# SCH_MIW_PS_on_PCB_2021-12-30.net
KiCad netlist of a schematic drawn in EasyEDA
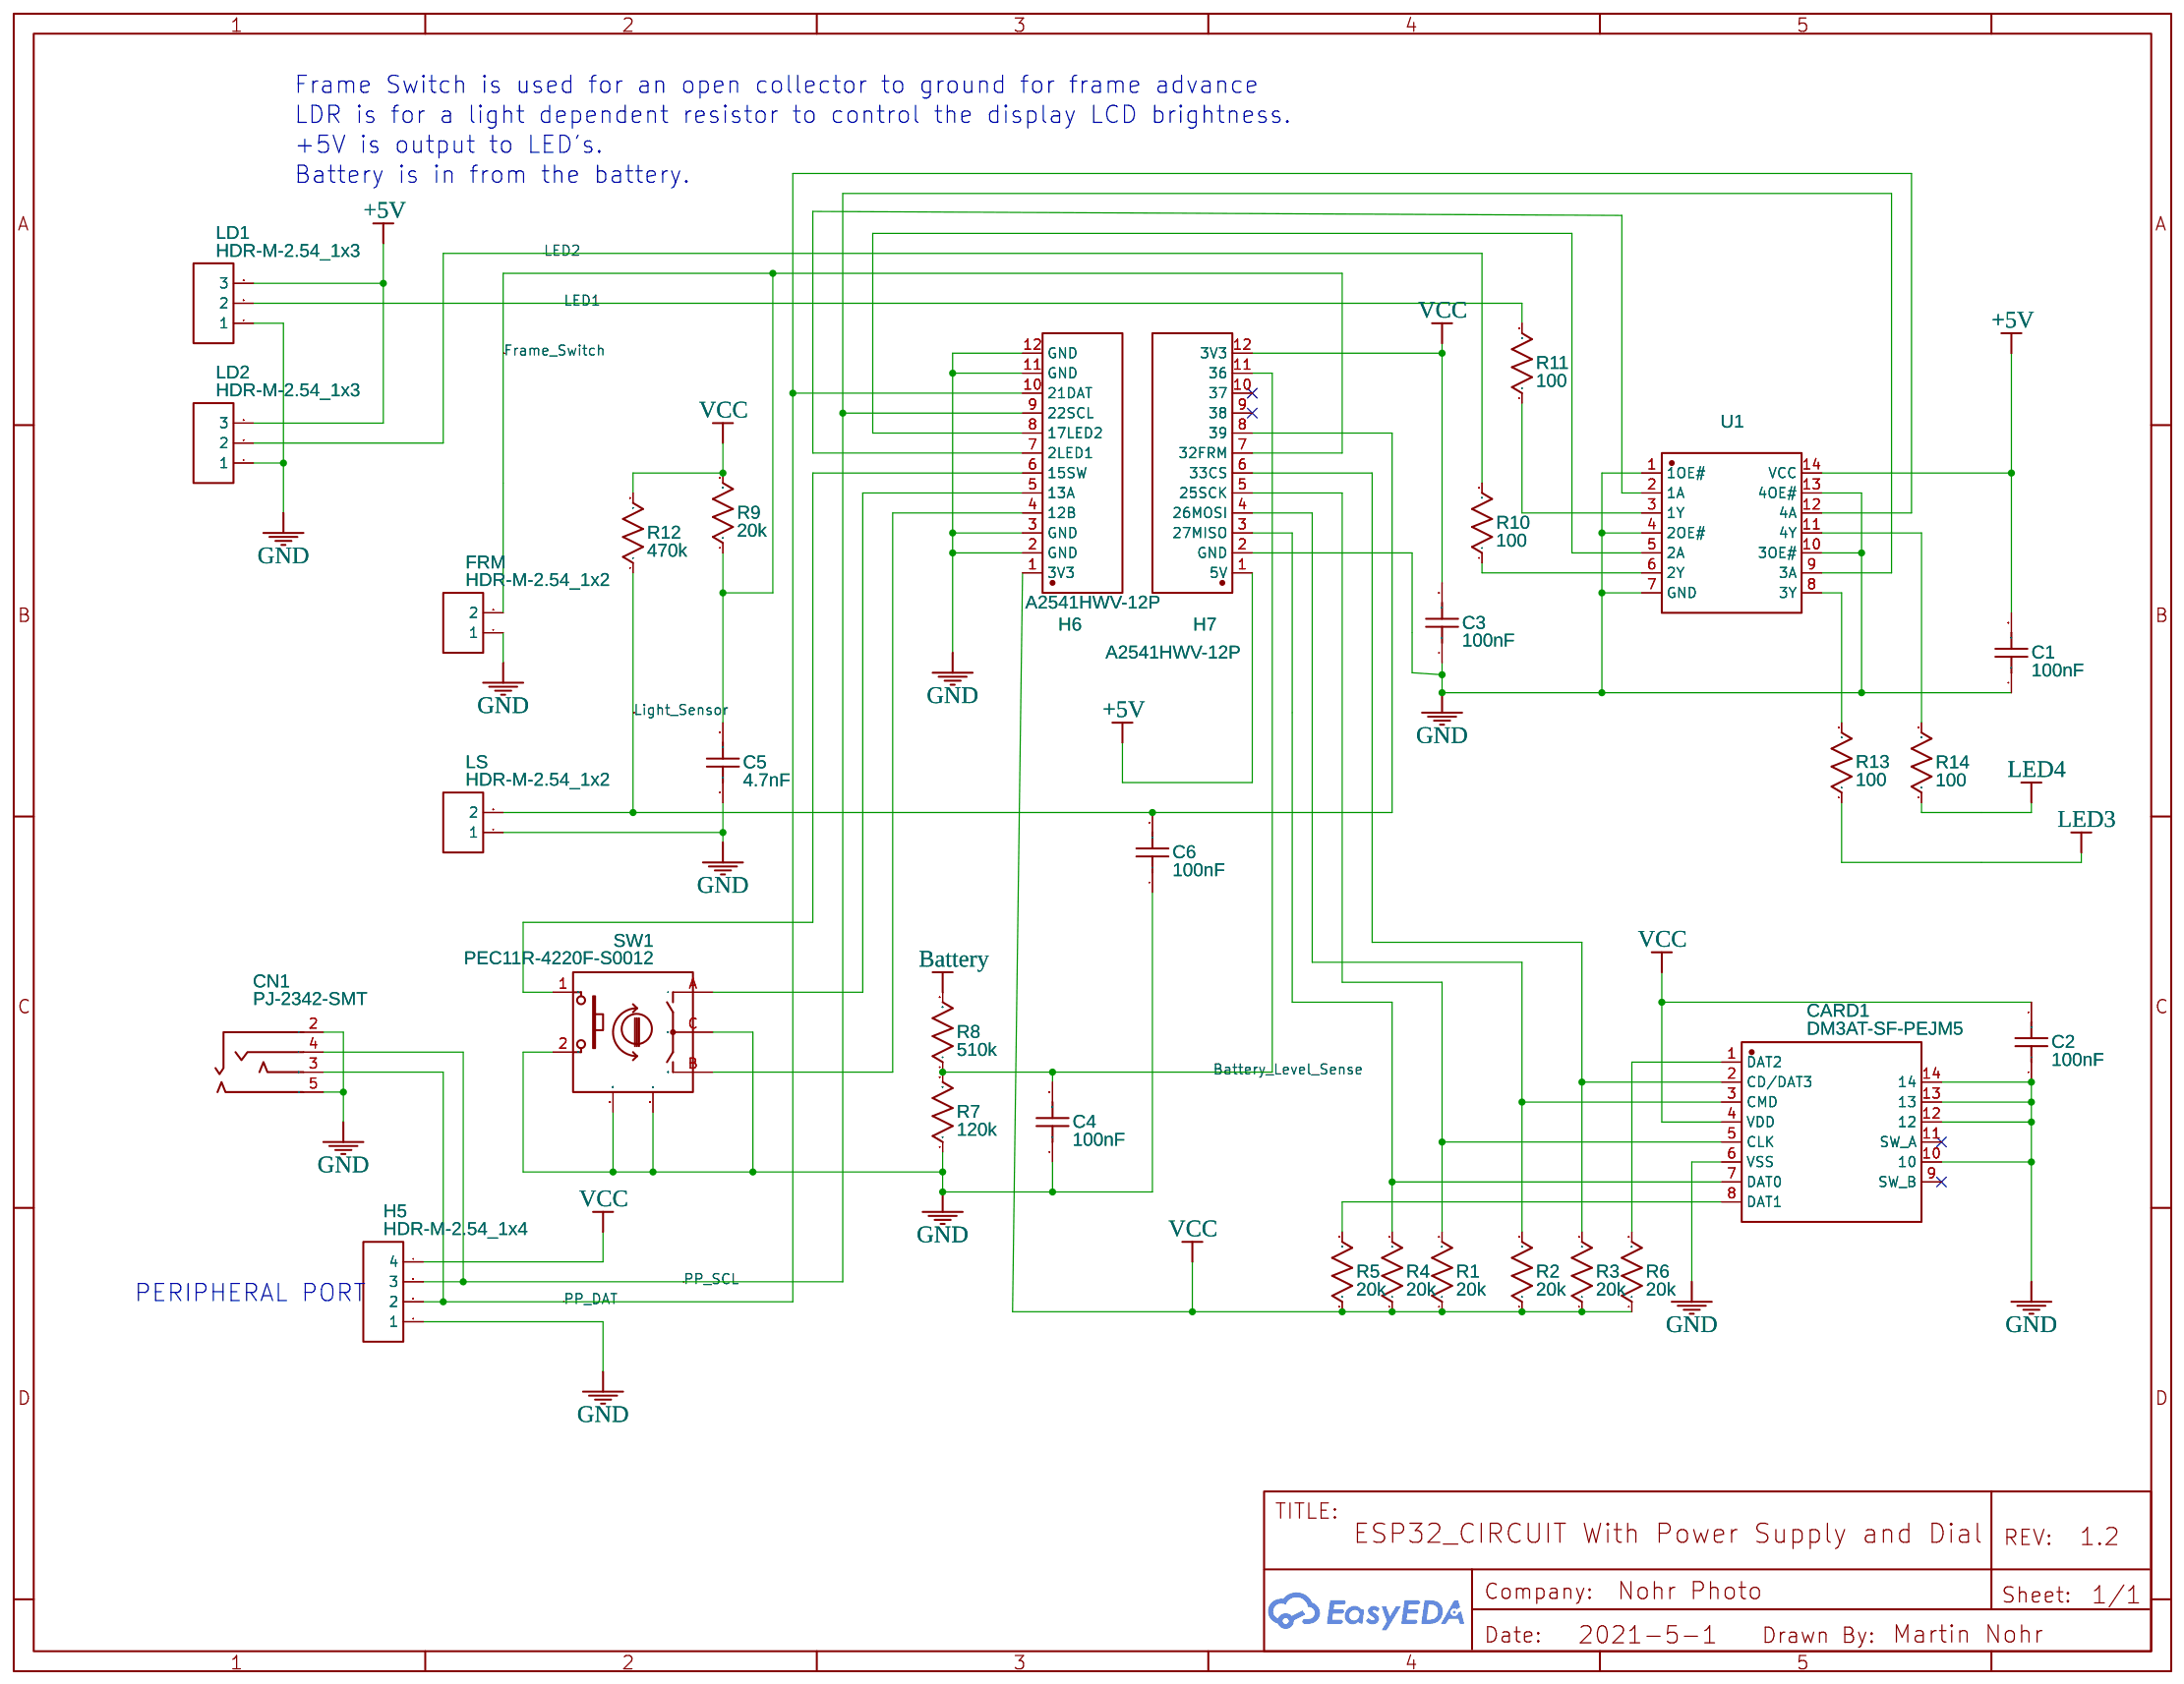
[diagram p0: TTGO_CIRCUIT_PCB_UNIFIED]
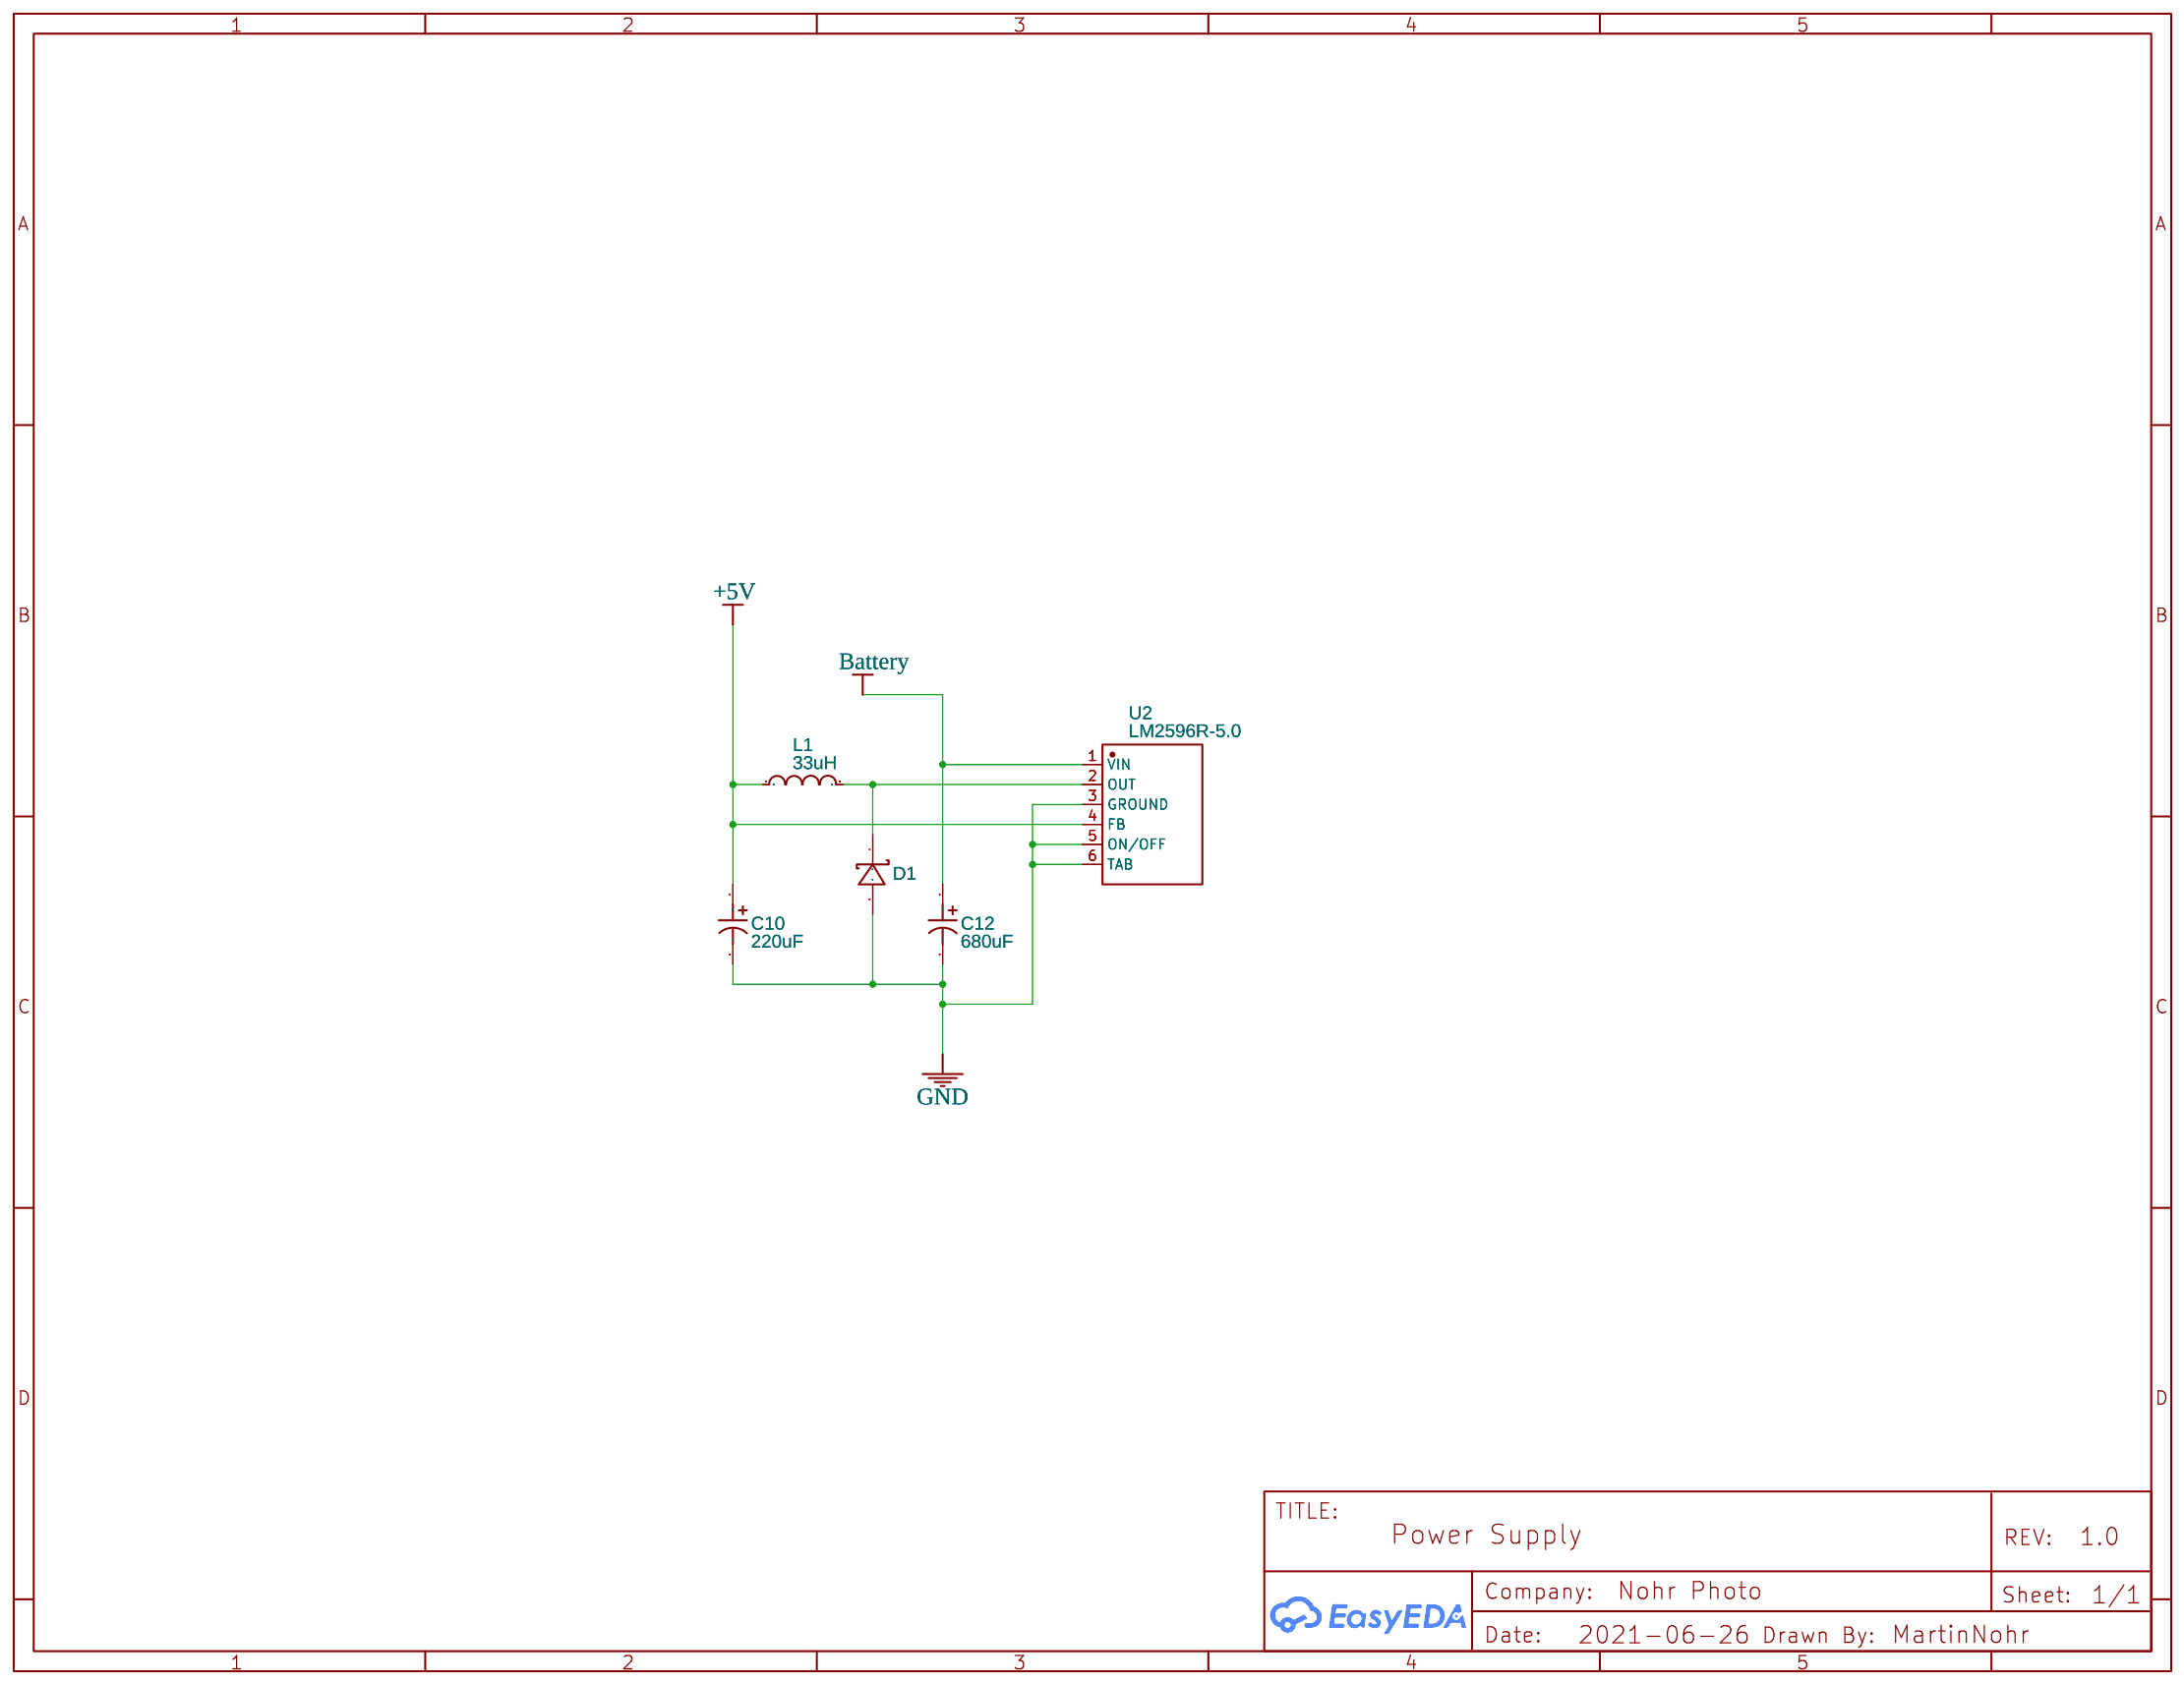
[diagram p1: Power Supply Circuit]

(export (version "E")
  (design (tool "Eeschema 10.0.6"))
  (components
    (comp (ref "C1")
      (value "100nF")
      (fields
        (field (name "BOM_Manufacturer Part") "CL10B104KC8NNNC")
        (field (name "BOM_Supplier Part") "C15725")
      )
      (libsource (lib "") (part "CL10B104KB8NFNC"))
    )
    (comp (ref "C2")
      (value "100nF")
      (fields
        (field (name "BOM_Manufacturer Part") "CL10B104KC8NNNC")
        (field (name "BOM_Supplier Part") "C15725")
      )
      (libsource (lib "") (part "CL10B104KB8NFNC"))
    )
    (comp (ref "C3")
      (value "100nF")
      (fields
        (field (name "BOM_Manufacturer Part") "CL10B104KC8NNNC")
        (field (name "BOM_Supplier Part") "C15725")
      )
      (libsource (lib "") (part "CL10B104KB8NFNC"))
    )
    (comp (ref "C4")
      (value "100nF")
      (fields
        (field (name "BOM_Manufacturer Part") "CL10B104KC8NNNC")
        (field (name "BOM_Supplier Part") "C15725")
      )
      (libsource (lib "") (part "CL10B104KB8NFNC"))
    )
    (comp (ref "C5")
      (value "4.7nF")
      (fields
        (field (name "BOM_Manufacturer Part") "CC0603KRX7R9BB472")
        (field (name "BOM_Supplier Part") "C106218")
      )
      (libsource (lib "") (part "CL10B104KB8NFNC"))
    )
    (comp (ref "C6")
      (value "100nF")
      (fields
        (field (name "BOM_Manufacturer Part") "CL10B104KC8NNNC")
        (field (name "BOM_Supplier Part") "C15725")
      )
      (libsource (lib "") (part "CL10B104KB8NFNC"))
    )
    (comp (ref "CARD1")
      (value "DM3AT-SF-PEJM5")
      (fields (field (name "BOM_Supplier Part") "C114218"))
      (libsource (lib "") (part "DM3AT-SF-PEJM5"))
    )
    (comp (ref "CN1")
      (value "PJ-2342-SMT")
      (fields (field (name "BOM_Supplier Part") "C397356"))
      (libsource (lib "") (part "PJ-2342-SMT"))
    )
    (comp (ref "FRM")
      (value "HDR-M-2.54_1x2")
      (fields (field (name "BOM_Supplier Part") "C124375"))
      (libsource (lib "") (part "HDR-M-2.54_1x2"))
    )
    (comp (ref "H5")
      (value "HDR-M-2.54_1x4")
      (fields (field (name "BOM_Supplier Part") "C124378"))
      (libsource (lib "") (part "HDR-F-2.54_1x4"))
    )
    (comp (ref "H6")
      (value "A2541HWV-12P")
      (fields (field (name "BOM_Supplier Part") "C225509"))
      (libsource (lib "") (part "A2541HWV-12P"))
    )
    (comp (ref "H7")
      (value "A2541HWV-12P")
      (fields (field (name "BOM_Supplier Part") "C225509"))
      (libsource (lib "") (part "A2541HWV-12P_1"))
    )
    (comp (ref "LD1")
      (value "HDR-M-2.54_1x3")
      (fields (field (name "BOM_Supplier Part") "C180248"))
      (libsource (lib "") (part "HDR-M-2.54_1x3"))
    )
    (comp (ref "LD2")
      (value "HDR-M-2.54_1x3")
      (fields (field (name "BOM_Supplier Part") "C180248"))
      (libsource (lib "") (part "HDR-M-2.54_1x3"))
    )
    (comp (ref "LS")
      (value "HDR-M-2.54_1x2")
      (fields (field (name "BOM_Supplier Part") "C124375"))
      (libsource (lib "") (part "HDR-M-2.54_1x2_1"))
    )
    (comp (ref "R1")
      (value "20k")
      (fields
        (field (name "BOM_Manufacturer Part") "0603WAF2002T5E")
        (field (name "BOM_Supplier Part") "C4184")
      )
      (libsource (lib "") (part "R_0603_US"))
    )
    (comp (ref "R2")
      (value "20k")
      (fields
        (field (name "BOM_Manufacturer Part") "0603WAF2002T5E")
        (field (name "BOM_Supplier Part") "C4184")
      )
      (libsource (lib "") (part "R_0603_US"))
    )
    (comp (ref "R3")
      (value "20k")
      (fields
        (field (name "BOM_Manufacturer Part") "0603WAF2002T5E")
        (field (name "BOM_Supplier Part") "C4184")
      )
      (libsource (lib "") (part "R_0603_US"))
    )
    (comp (ref "R4")
      (value "20k")
      (fields
        (field (name "BOM_Manufacturer Part") "0603WAF2002T5E")
        (field (name "BOM_Supplier Part") "C4184")
      )
      (libsource (lib "") (part "R_0603_US"))
    )
    (comp (ref "R5")
      (value "20k")
      (fields
        (field (name "BOM_Manufacturer Part") "0603WAF2002T5E")
        (field (name "BOM_Supplier Part") "C4184")
      )
      (libsource (lib "") (part "R_0603_US"))
    )
    (comp (ref "R6")
      (value "20k")
      (fields
        (field (name "BOM_Manufacturer Part") "0603WAF2002T5E")
        (field (name "BOM_Supplier Part") "C4184")
      )
      (libsource (lib "") (part "R_0603_US"))
    )
    (comp (ref "R7")
      (value "120k")
      (fields
        (field (name "BOM_Manufacturer Part") "0603WAF1203T5E")
        (field (name "BOM_Supplier Part") "C25808")
      )
      (libsource (lib "") (part "R_0603_US"))
    )
    (comp (ref "R8")
      (value "510k")
      (fields
        (field (name "BOM_Manufacturer Part") "0603WAF5103T5E")
        (field (name "BOM_Supplier Part") "C23192")
      )
      (libsource (lib "") (part "R_0603_US"))
    )
    (comp (ref "R9")
      (value "20k")
      (fields
        (field (name "BOM_Manufacturer Part") "0603WAF2002T5E")
        (field (name "BOM_Supplier Part") "C4184")
      )
      (libsource (lib "") (part "R_0603_US"))
    )
    (comp (ref "R10")
      (value "100")
      (fields
        (field (name "BOM_Manufacturer Part") "0603WAF1000T5E")
        (field (name "BOM_Supplier Part") "C22775")
      )
      (libsource (lib "") (part "R_0603_US"))
    )
    (comp (ref "R11")
      (value "100")
      (fields
        (field (name "BOM_Manufacturer Part") "0603WAF1000T5E")
        (field (name "BOM_Supplier Part") "C22775")
      )
      (libsource (lib "") (part "R_0603_US"))
    )
    (comp (ref "R12")
      (value "470k")
      (fields
        (field (name "BOM_Manufacturer Part") "0603WAF4703T5E")
        (field (name "BOM_Supplier Part") "C23178")
      )
      (libsource (lib "") (part "R_0603_US"))
    )
    (comp (ref "R13")
      (value "100")
      (fields
        (field (name "BOM_Manufacturer Part") "0603WAF1000T5E")
        (field (name "BOM_Supplier Part") "C22775")
      )
      (libsource (lib "") (part "R_0603_US"))
    )
    (comp (ref "R14")
      (value "100")
      (fields
        (field (name "BOM_Manufacturer Part") "0603WAF1000T5E")
        (field (name "BOM_Supplier Part") "C22775")
      )
      (libsource (lib "") (part "R_0603_US"))
    )
    (comp (ref "SW1")
      (value "PEC11R-4220F-S0012")
      (fields (field (name "BOM_Supplier Part") "C143817"))
      (libsource (lib "") (part "PEC11R-4015F-S0024"))
    )
    (comp (ref "U1")
      (value "74HCT125PW,112")
      (fields (field (name "BOM_Supplier Part") "C545657"))
      (libsource (lib "") (part "74HCT125PW,112"))
    )
    (comp (ref "C10")
      (value "220uF")
      (fields
        (field (name "BOM_Manufacturer Part") "220uF 16V 6.3*7")
        (field (name "BOM_Supplier Part") "C43340")
      )
      (libsource (lib "") (part "160ARCP221M05X8P00"))
    )
    (comp (ref "C12")
      (value "680uF")
      (fields
        (field (name "BOM_Manufacturer Part") "SPT1EM681F12OR")
        (field (name "BOM_Supplier Part") "C698148")
      )
      (libsource (lib "") (part "SPT1EM681F12OR"))
    )
    (comp (ref "D1")
      (value "B2100-13-F")
      (fields (field (name "BOM_Supplier Part") "C110479"))
      (libsource (lib "") (part "B2100-13-F"))
    )
    (comp (ref "L1")
      (value "33uH")
      (fields
        (field (name "BOM_Manufacturer Part") "YSPI1050-330M")
        (field (name "BOM_Supplier Part") "C497900")
      )
      (libsource (lib "") (part "YSPI1050-330M"))
    )
    (comp (ref "U2")
      (value "LM2596R-5.0")
      (fields (field (name "BOM_Supplier Part") "C77782"))
      (libsource (lib "") (part "LM2596R-5.0"))
    )
  )
  (nets
    (net (code "1") (name "+5V") (class "Default")
      (node (ref "C1") (pin "2") (pinfunction "2_2") (pintype "unspecified"))
      (node (ref "C10") (pin "1") (pinfunction "1_1") (pintype "input"))
      (node (ref "H7") (pin "1") (pinfunction "5V_1") (pintype "unspecified"))
      (node (ref "L1") (pin "1") (pinfunction "1_1") (pintype "unspecified"))
      (node (ref "LD1") (pin "3") (pinfunction "3_3") (pintype "input"))
      (node (ref "LD2") (pin "3") (pinfunction "3_3") (pintype "input"))
      (node (ref "U1") (pin "14") (pinfunction "VCC_14") (pintype "unspecified"))
      (node (ref "U2") (pin "4") (pinfunction "FB_4") (pintype "unspecified"))
    )
    (net (code "2") (name "Battery") (class "Default")
      (node (ref "C12") (pin "1") (pinfunction "1_1") (pintype "input"))
      (node (ref "R8") (pin "2") (pinfunction "2_2") (pintype "unspecified"))
      (node (ref "U2") (pin "1") (pinfunction "VIN_1") (pintype "unspecified"))
    )
    (net (code "3") (name "Battery_Level_Sense") (class "Default")
      (node (ref "C4") (pin "2") (pinfunction "2_2") (pintype "unspecified"))
      (node (ref "H7") (pin "11") (pinfunction "36_11") (pintype "unspecified"))
      (node (ref "R7") (pin "2") (pinfunction "2_2") (pintype "unspecified"))
      (node (ref "R8") (pin "1") (pinfunction "1_1") (pintype "unspecified"))
    )
    (net (code "4") (name "Frame_Switch") (class "Default")
      (node (ref "C5") (pin "2") (pinfunction "2_2") (pintype "unspecified"))
      (node (ref "FRM") (pin "2") (pinfunction "2_2") (pintype "unspecified"))
      (node (ref "H7") (pin "7") (pinfunction "32FRM_7") (pintype "unspecified"))
      (node (ref "R9") (pin "1") (pinfunction "1_1") (pintype "unspecified"))
    )
    (net (code "5") (name "GND") (class "Default")
      (node (ref "C1") (pin "1") (pinfunction "1_1") (pintype "unspecified"))
      (node (ref "C10") (pin "2") (pinfunction "2_2") (pintype "input"))
      (node (ref "C12") (pin "2") (pinfunction "2_2") (pintype "input"))
      (node (ref "C2") (pin "1") (pinfunction "1_1") (pintype "unspecified"))
      (node (ref "C3") (pin "1") (pinfunction "1_1") (pintype "unspecified"))
      (node (ref "C4") (pin "1") (pinfunction "1_1") (pintype "unspecified"))
      (node (ref "C5") (pin "1") (pinfunction "1_1") (pintype "unspecified"))
      (node (ref "C6") (pin "1") (pinfunction "1_1") (pintype "unspecified"))
      (node (ref "CARD1") (pin "10") (pinfunction "10_10") (pintype "unspecified"))
      (node (ref "CARD1") (pin "12") (pinfunction "12_12") (pintype "unspecified"))
      (node (ref "CARD1") (pin "13") (pinfunction "13_13") (pintype "unspecified"))
      (node (ref "CARD1") (pin "14") (pinfunction "14_14") (pintype "unspecified"))
      (node (ref "CARD1") (pin "6") (pinfunction "VSS_6") (pintype "unspecified"))
      (node (ref "CN1") (pin "2") (pinfunction "2_2") (pintype "unspecified"))
      (node (ref "CN1") (pin "5") (pinfunction "5_5") (pintype "unspecified"))
      (node (ref "D1") (pin "2") (pinfunction "2_2") (pintype "unspecified"))
      (node (ref "FRM") (pin "1") (pinfunction "1_1") (pintype "unspecified"))
      (node (ref "H5") (pin "1") (pinfunction "1_1") (pintype "unspecified"))
      (node (ref "H6") (pin "11") (pinfunction "GND_11") (pintype "unspecified"))
      (node (ref "H6") (pin "12") (pinfunction "GND_12") (pintype "unspecified"))
      (node (ref "H6") (pin "2") (pinfunction "GND_2") (pintype "unspecified"))
      (node (ref "H6") (pin "3") (pinfunction "GND_3") (pintype "unspecified"))
      (node (ref "H7") (pin "2") (pinfunction "GND_2") (pintype "unspecified"))
      (node (ref "LD1") (pin "1") (pinfunction "1_1") (pintype "input"))
      (node (ref "LD2") (pin "1") (pinfunction "1_1") (pintype "input"))
      (node (ref "LS") (pin "1") (pinfunction "1_1") (pintype "unspecified"))
      (node (ref "R7") (pin "1") (pinfunction "1_1") (pintype "unspecified"))
      (node (ref "SW1") (pin "2") (pinfunction "2_2") (pintype "unspecified"))
      (node (ref "SW1") (pin "C") (pinfunction "C_C") (pintype "unspecified"))
      (node (ref "SW1") (pin "MT1") (pinfunction "MT1_MT1") (pintype "unspecified"))
      (node (ref "SW1") (pin "MT2") (pinfunction "MT2_MT2") (pintype "unspecified"))
      (node (ref "U1") (pin "1") (pinfunction "1OE#_1") (pintype "unspecified"))
      (node (ref "U1") (pin "10") (pinfunction "3OE#_10") (pintype "unspecified"))
      (node (ref "U1") (pin "13") (pinfunction "4OE#_13") (pintype "unspecified"))
      (node (ref "U1") (pin "4") (pinfunction "2OE#_4") (pintype "unspecified"))
      (node (ref "U1") (pin "7") (pinfunction "GND_7") (pintype "unspecified"))
      (node (ref "U2") (pin "3") (pinfunction "GROUND_3") (pintype "unspecified"))
      (node (ref "U2") (pin "5") (pinfunction "ON/OFF_5") (pintype "unspecified"))
      (node (ref "U2") (pin "6") (pinfunction "TAB_6") (pintype "unspecified"))
    )
    (net (code "6") (name "LED1") (class "Default")
      (node (ref "LD1") (pin "2") (pinfunction "2_2") (pintype "input"))
      (node (ref "R11") (pin "2") (pinfunction "2_2") (pintype "unspecified"))
    )
    (net (code "7") (name "LED2") (class "Default")
      (node (ref "LD2") (pin "2") (pinfunction "2_2") (pintype "input"))
      (node (ref "R10") (pin "2") (pinfunction "2_2") (pintype "unspecified"))
    )
    (net (code "8") (name "LED3") (class "Default")
      (node (ref "R13") (pin "1") (pinfunction "1_1") (pintype "unspecified"))
    )
    (net (code "9") (name "LED4") (class "Default")
      (node (ref "R14") (pin "1") (pinfunction "1_1") (pintype "unspecified"))
    )
    (net (code "10") (name "Light_Sensor") (class "Default")
      (node (ref "C6") (pin "2") (pinfunction "2_2") (pintype "unspecified"))
      (node (ref "H7") (pin "8") (pinfunction "39_8") (pintype "unspecified"))
      (node (ref "LS") (pin "2") (pinfunction "2_2") (pintype "unspecified"))
      (node (ref "R12") (pin "1") (pinfunction "1_1") (pintype "unspecified"))
    )
    (net (code "11") (name "Net-(CARD1-CD{slash}DAT3)") (class "Default")
      (node (ref "CARD1") (pin "2") (pinfunction "CD/DAT3_2") (pintype "unspecified"))
      (node (ref "H7") (pin "6") (pinfunction "33CS_6") (pintype "unspecified"))
      (node (ref "R3") (pin "2") (pinfunction "2_2") (pintype "unspecified"))
    )
    (net (code "12") (name "Net-(CARD1-CLK)") (class "Default")
      (node (ref "CARD1") (pin "5") (pinfunction "CLK_5") (pintype "unspecified"))
      (node (ref "H7") (pin "5") (pinfunction "25SCK_5") (pintype "unspecified"))
      (node (ref "R1") (pin "2") (pinfunction "2_2") (pintype "unspecified"))
    )
    (net (code "13") (name "Net-(CARD1-CMD)") (class "Default")
      (node (ref "CARD1") (pin "3") (pinfunction "CMD_3") (pintype "unspecified"))
      (node (ref "H7") (pin "4") (pinfunction "26MOSI_4") (pintype "unspecified"))
      (node (ref "R2") (pin "2") (pinfunction "2_2") (pintype "unspecified"))
    )
    (net (code "14") (name "Net-(CARD1-DAT0)") (class "Default")
      (node (ref "CARD1") (pin "7") (pinfunction "DAT0_7") (pintype "unspecified"))
      (node (ref "H7") (pin "3") (pinfunction "27MISO_3") (pintype "unspecified"))
      (node (ref "R4") (pin "2") (pinfunction "2_2") (pintype "unspecified"))
    )
    (net (code "15") (name "Net-(CARD1-DAT1)") (class "Default")
      (node (ref "CARD1") (pin "8") (pinfunction "DAT1_8") (pintype "unspecified"))
      (node (ref "R5") (pin "2") (pinfunction "2_2") (pintype "unspecified"))
    )
    (net (code "16") (name "Net-(CARD1-DAT2)") (class "Default")
      (node (ref "CARD1") (pin "1") (pinfunction "DAT2_1") (pintype "unspecified"))
      (node (ref "R6") (pin "2") (pinfunction "2_2") (pintype "unspecified"))
    )
    (net (code "17") (name "Net-(H6-2LED1)") (class "Default")
      (node (ref "H6") (pin "7") (pinfunction "2LED1_7") (pintype "unspecified"))
      (node (ref "U1") (pin "2") (pinfunction "1A_2") (pintype "unspecified"))
    )
    (net (code "18") (name "Net-(H6-12B)") (class "Default")
      (node (ref "H6") (pin "4") (pinfunction "12B_4") (pintype "unspecified"))
      (node (ref "SW1") (pin "B") (pinfunction "B_B") (pintype "unspecified"))
    )
    (net (code "19") (name "Net-(H6-13A)") (class "Default")
      (node (ref "H6") (pin "5") (pinfunction "13A_5") (pintype "unspecified"))
      (node (ref "SW1") (pin "A") (pinfunction "A_A") (pintype "unspecified"))
    )
    (net (code "20") (name "Net-(H6-15SW)") (class "Default")
      (node (ref "H6") (pin "6") (pinfunction "15SW_6") (pintype "unspecified"))
      (node (ref "SW1") (pin "1") (pinfunction "1_1") (pintype "unspecified"))
    )
    (net (code "21") (name "Net-(H6-17LED2)") (class "Default")
      (node (ref "H6") (pin "8") (pinfunction "17LED2_8") (pintype "unspecified"))
      (node (ref "U1") (pin "5") (pinfunction "2A_5") (pintype "unspecified"))
    )
    (net (code "22") (name "Net-(U1-1Y)") (class "Default")
      (node (ref "R11") (pin "1") (pinfunction "1_1") (pintype "unspecified"))
      (node (ref "U1") (pin "3") (pinfunction "1Y_3") (pintype "unspecified"))
    )
    (net (code "23") (name "Net-(U1-2Y)") (class "Default")
      (node (ref "R10") (pin "1") (pinfunction "1_1") (pintype "unspecified"))
      (node (ref "U1") (pin "6") (pinfunction "2Y_6") (pintype "unspecified"))
    )
    (net (code "24") (name "Net-(U1-3Y)") (class "Default")
      (node (ref "R13") (pin "2") (pinfunction "2_2") (pintype "unspecified"))
      (node (ref "U1") (pin "8") (pinfunction "3Y_8") (pintype "unspecified"))
    )
    (net (code "25") (name "Net-(U1-4Y)") (class "Default")
      (node (ref "R14") (pin "2") (pinfunction "2_2") (pintype "unspecified"))
      (node (ref "U1") (pin "11") (pinfunction "4Y_11") (pintype "unspecified"))
    )
    (net (code "26") (name "Net-(U2-OUT)") (class "Default")
      (node (ref "D1") (pin "1") (pinfunction "1_1") (pintype "unspecified"))
      (node (ref "L1") (pin "2") (pinfunction "2_2") (pintype "unspecified"))
      (node (ref "U2") (pin "2") (pinfunction "OUT_2") (pintype "unspecified"))
    )
    (net (code "27") (name "PP_DAT") (class "Default")
      (node (ref "CN1") (pin "3") (pinfunction "3_3") (pintype "unspecified"))
      (node (ref "H5") (pin "2") (pinfunction "2_2") (pintype "unspecified"))
      (node (ref "H6") (pin "10") (pinfunction "21DAT_10") (pintype "unspecified"))
      (node (ref "U1") (pin "12") (pinfunction "4A_12") (pintype "unspecified"))
    )
    (net (code "28") (name "PP_SCL") (class "Default")
      (node (ref "CN1") (pin "4") (pinfunction "4_4") (pintype "unspecified"))
      (node (ref "H5") (pin "3") (pinfunction "3_3") (pintype "unspecified"))
      (node (ref "H6") (pin "9") (pinfunction "22SCL_9") (pintype "unspecified"))
      (node (ref "U1") (pin "9") (pinfunction "3A_9") (pintype "unspecified"))
    )
    (net (code "29") (name "VCC") (class "Default")
      (node (ref "C2") (pin "2") (pinfunction "2_2") (pintype "unspecified"))
      (node (ref "C3") (pin "2") (pinfunction "2_2") (pintype "unspecified"))
      (node (ref "CARD1") (pin "4") (pinfunction "VDD_4") (pintype "unspecified"))
      (node (ref "H5") (pin "4") (pinfunction "4_4") (pintype "unspecified"))
      (node (ref "H6") (pin "1") (pinfunction "3V3_1") (pintype "unspecified"))
      (node (ref "H7") (pin "12") (pinfunction "3V3_12") (pintype "unspecified"))
      (node (ref "R1") (pin "1") (pinfunction "1_1") (pintype "unspecified"))
      (node (ref "R12") (pin "2") (pinfunction "2_2") (pintype "unspecified"))
      (node (ref "R2") (pin "1") (pinfunction "1_1") (pintype "unspecified"))
      (node (ref "R3") (pin "1") (pinfunction "1_1") (pintype "unspecified"))
      (node (ref "R4") (pin "1") (pinfunction "1_1") (pintype "unspecified"))
      (node (ref "R5") (pin "1") (pinfunction "1_1") (pintype "unspecified"))
      (node (ref "R6") (pin "1") (pinfunction "1_1") (pintype "unspecified"))
      (node (ref "R9") (pin "2") (pinfunction "2_2") (pintype "unspecified"))
    )
    (net (code "30") (name "unconnected-(CARD1-SW_A-Pad11)") (class "Default")
      (node (ref "CARD1") (pin "11") (pinfunction "SW_A_11") (pintype "unspecified+no_connect"))
    )
    (net (code "31") (name "unconnected-(CARD1-SW_B-Pad9)") (class "Default")
      (node (ref "CARD1") (pin "9") (pinfunction "SW_B_9") (pintype "unspecified+no_connect"))
    )
    (net (code "32") (name "unconnected-(H7-37-Pad10)") (class "Default")
      (node (ref "H7") (pin "10") (pinfunction "37_10") (pintype "unspecified+no_connect"))
    )
    (net (code "33") (name "unconnected-(H7-38-Pad9)") (class "Default")
      (node (ref "H7") (pin "9") (pinfunction "38_9") (pintype "unspecified+no_connect"))
    )
  )
)
